# rotenc.net
KiCad netlist of a schematic drawn in EAGLE
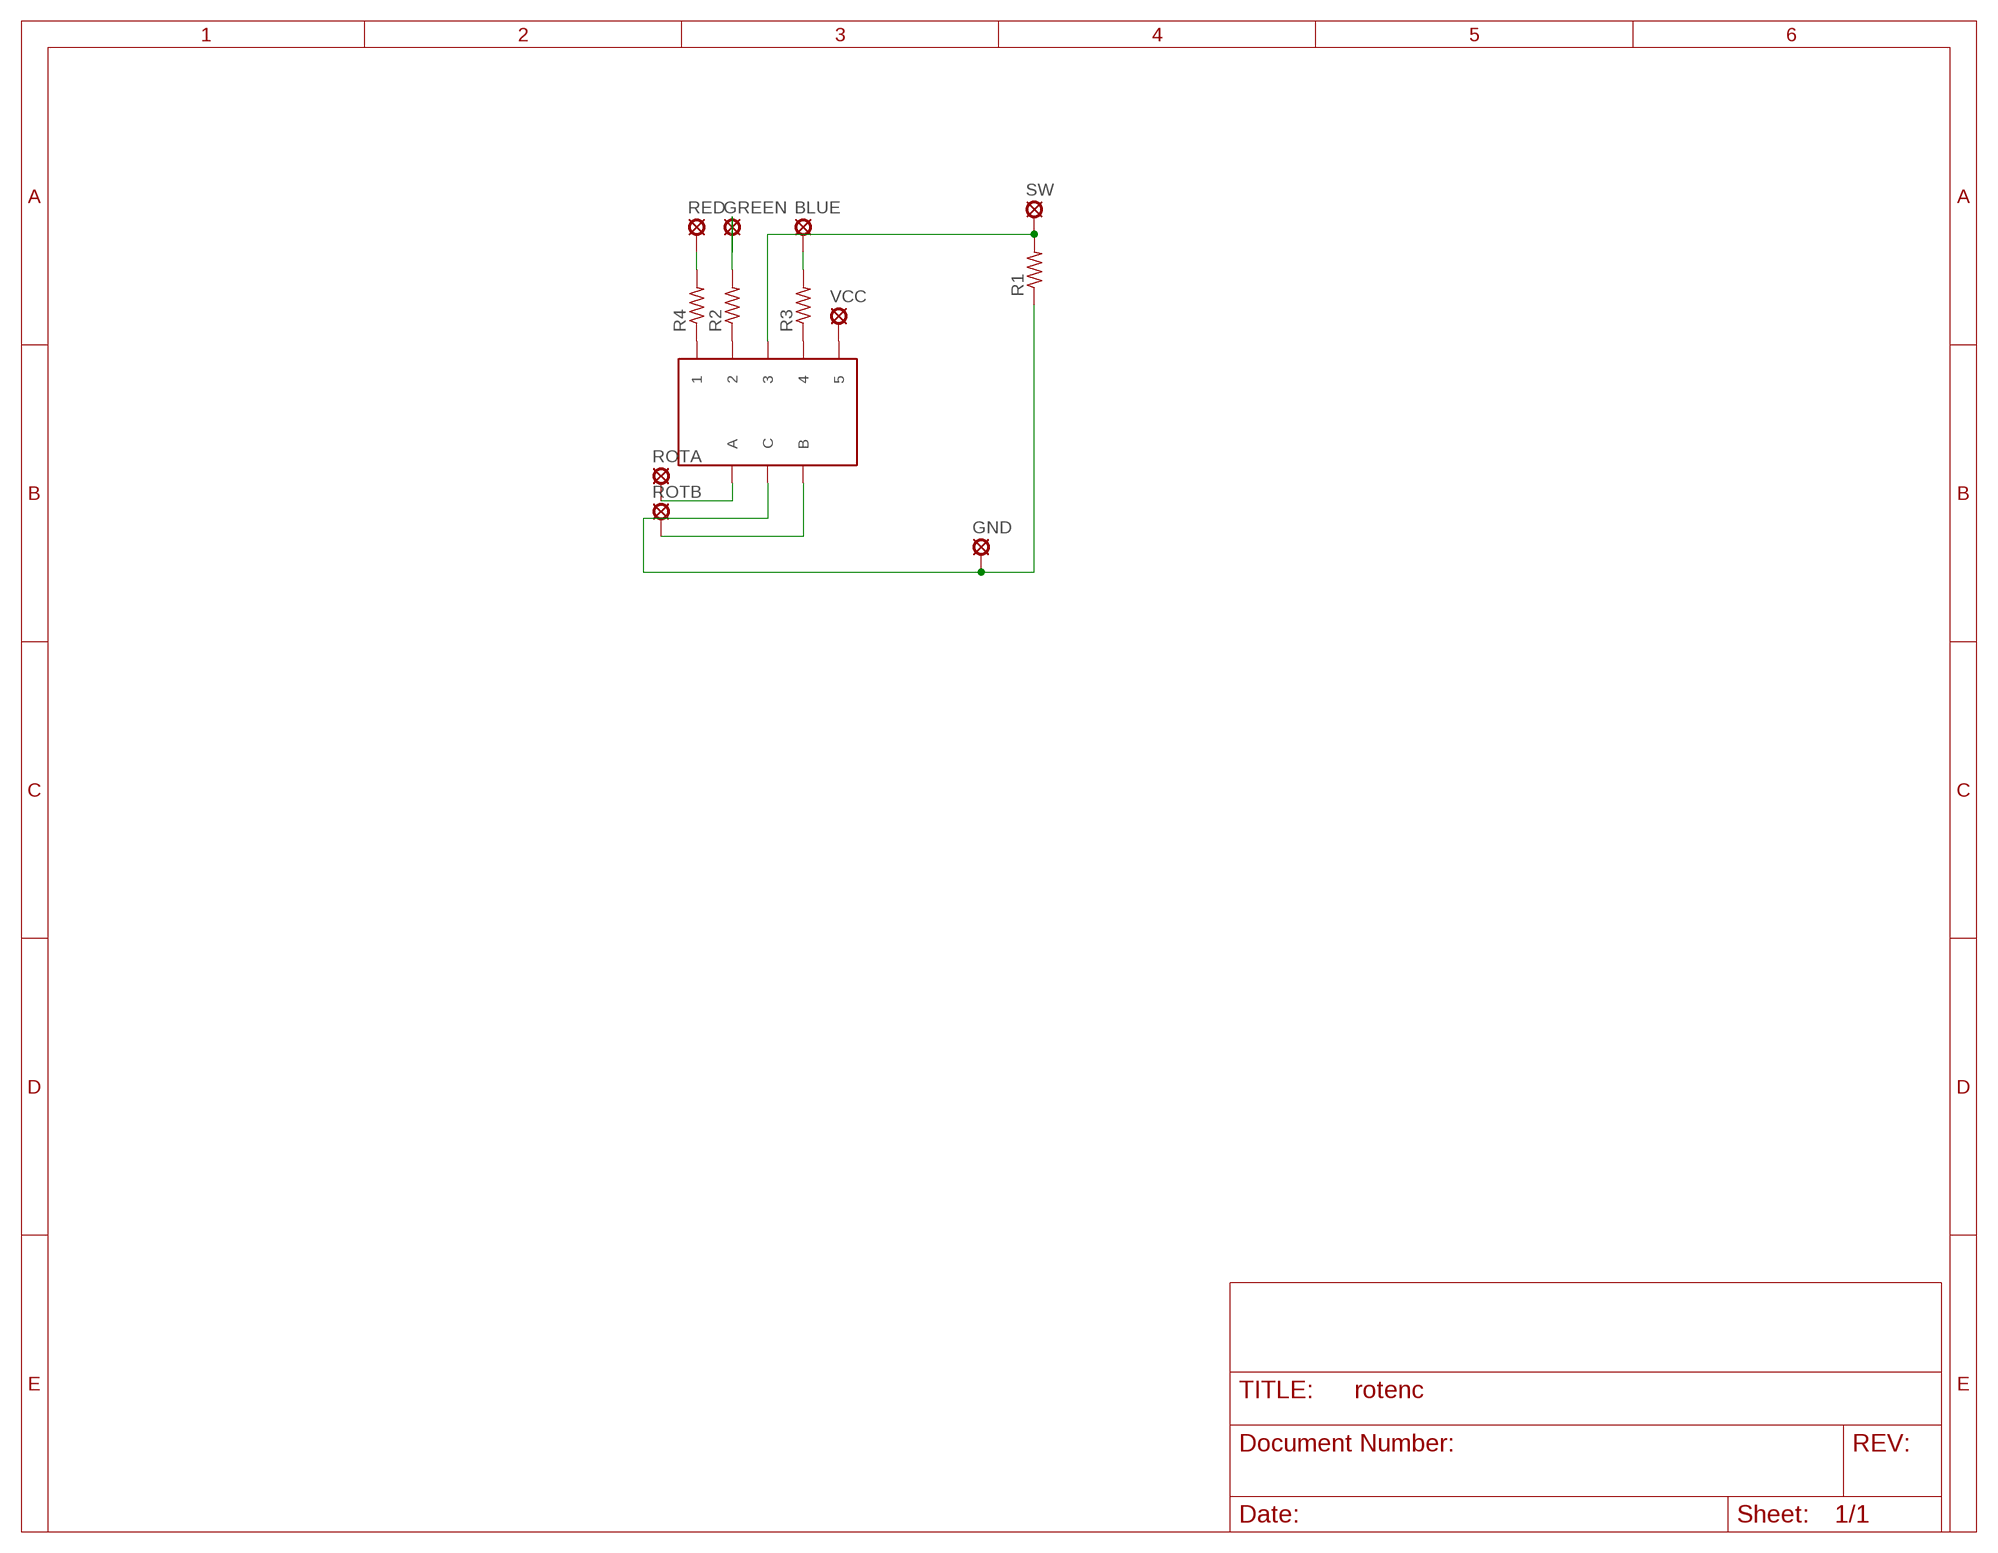
[diagram p0: schematic, sheet 1]

(export (version "E")
  (design (tool "Eeschema 10.0.6"))
  (components
    (comp (ref "BLUE")
      (value "SE13")
      (footprint "eagle-import:SE13")
      (libsource (lib "eagle-import") (part "SE13"))
    )
    (comp (ref "GND")
      (value "SE13")
      (footprint "eagle-import:SE13")
      (libsource (lib "eagle-import") (part "SE13"))
    )
    (comp (ref "GREEN")
      (value "SE13")
      (footprint "eagle-import:SE13")
      (libsource (lib "eagle-import") (part "SE13"))
    )
    (comp (ref "R1")
      (value "R-US_0207/7")
      (footprint "eagle-import:0207_7")
      (libsource (lib "eagle-import") (part "R-US_0207/7"))
    )
    (comp (ref "R2")
      (value "R-US_0207/7")
      (footprint "eagle-import:0207_7")
      (libsource (lib "eagle-import") (part "R-US_0207/7"))
    )
    (comp (ref "R3")
      (value "R-US_0207/7")
      (footprint "eagle-import:0207_7")
      (libsource (lib "eagle-import") (part "R-US_0207/7"))
    )
    (comp (ref "R4")
      (value "R-US_0207/7")
      (footprint "eagle-import:0207_7")
      (libsource (lib "eagle-import") (part "R-US_0207/7"))
    )
    (comp (ref "RED")
      (value "SE13")
      (footprint "eagle-import:SE13")
      (libsource (lib "eagle-import") (part "SE13"))
    )
    (comp (ref "ROTA")
      (value "SE13")
      (footprint "eagle-import:SE13")
      (libsource (lib "eagle-import") (part "SE13"))
    )
    (comp (ref "ROTB")
      (value "SE13")
      (footprint "eagle-import:SE13")
      (libsource (lib "eagle-import") (part "SE13"))
    )
    (comp (ref "SW")
      (value "SE13")
      (footprint "eagle-import:SE13")
      (libsource (lib "eagle-import") (part "SE13"))
    )
    (comp (ref "U$1")
      (value "EC12PLRGB")
      (footprint "eagle-import:EL1296RGB")
      (libsource (lib "eagle-import") (part "EC12PLRGB"))
    )
    (comp (ref "VCC")
      (value "SE13")
      (footprint "eagle-import:SE13")
      (libsource (lib "eagle-import") (part "SE13"))
    )
  )
  (nets
    (net (code "1") (name "Net-(BLUE-PadMP)") (class "Default")
      (node (ref "BLUE") (pin "MP") (pinfunction "MP_MP") (pintype "passive"))
      (node (ref "R3") (pin "2") (pinfunction "2_2") (pintype "passive"))
    )
    (net (code "2") (name "Net-(GND-PadMP)") (class "Default")
      (node (ref "GND") (pin "MP") (pinfunction "MP_MP") (pintype "passive"))
      (node (ref "R1") (pin "1") (pinfunction "1_1") (pintype "passive"))
      (node (ref "U$1") (pin "C") (pinfunction "C_C") (pintype "bidirectional"))
    )
    (net (code "3") (name "Net-(GREEN-PadMP)") (class "Default")
      (node (ref "GREEN") (pin "MP") (pinfunction "MP_MP") (pintype "passive"))
      (node (ref "R2") (pin "2") (pinfunction "2_2") (pintype "passive"))
    )
    (net (code "4") (name "Net-(R1-Pad2)") (class "Default")
      (node (ref "R1") (pin "2") (pinfunction "2_2") (pintype "passive"))
      (node (ref "SW") (pin "MP") (pinfunction "MP_MP") (pintype "passive"))
      (node (ref "U$1") (pin "3") (pinfunction "3_3") (pintype "bidirectional"))
    )
    (net (code "5") (name "Net-(R2-Pad1)") (class "Default")
      (node (ref "R2") (pin "1") (pinfunction "1_1") (pintype "passive"))
      (node (ref "U$1") (pin "2") (pinfunction "2_2") (pintype "bidirectional"))
    )
    (net (code "6") (name "Net-(R3-Pad1)") (class "Default")
      (node (ref "R3") (pin "1") (pinfunction "1_1") (pintype "passive"))
      (node (ref "U$1") (pin "4") (pinfunction "4_4") (pintype "bidirectional"))
    )
    (net (code "7") (name "Net-(R4-Pad1)") (class "Default")
      (node (ref "R4") (pin "1") (pinfunction "1_1") (pintype "passive"))
      (node (ref "U$1") (pin "1") (pinfunction "1_1") (pintype "bidirectional"))
    )
    (net (code "8") (name "Net-(R4-Pad2)") (class "Default")
      (node (ref "R4") (pin "2") (pinfunction "2_2") (pintype "passive"))
      (node (ref "RED") (pin "MP") (pinfunction "MP_MP") (pintype "passive"))
    )
    (net (code "9") (name "Net-(ROTA-PadMP)") (class "Default")
      (node (ref "ROTA") (pin "MP") (pinfunction "MP_MP") (pintype "passive"))
      (node (ref "U$1") (pin "A") (pinfunction "A_A") (pintype "bidirectional"))
    )
    (net (code "10") (name "Net-(ROTB-PadMP)") (class "Default")
      (node (ref "ROTB") (pin "MP") (pinfunction "MP_MP") (pintype "passive"))
      (node (ref "U$1") (pin "B") (pinfunction "B_B") (pintype "bidirectional"))
    )
    (net (code "11") (name "Net-(U$1-Pad5)") (class "Default")
      (node (ref "U$1") (pin "5") (pinfunction "5_5") (pintype "bidirectional"))
      (node (ref "VCC") (pin "MP") (pinfunction "MP_MP") (pintype "passive"))
    )
  )
)
